# design.net
KiCad netlist of a schematic drawn in EasyEDA Pro
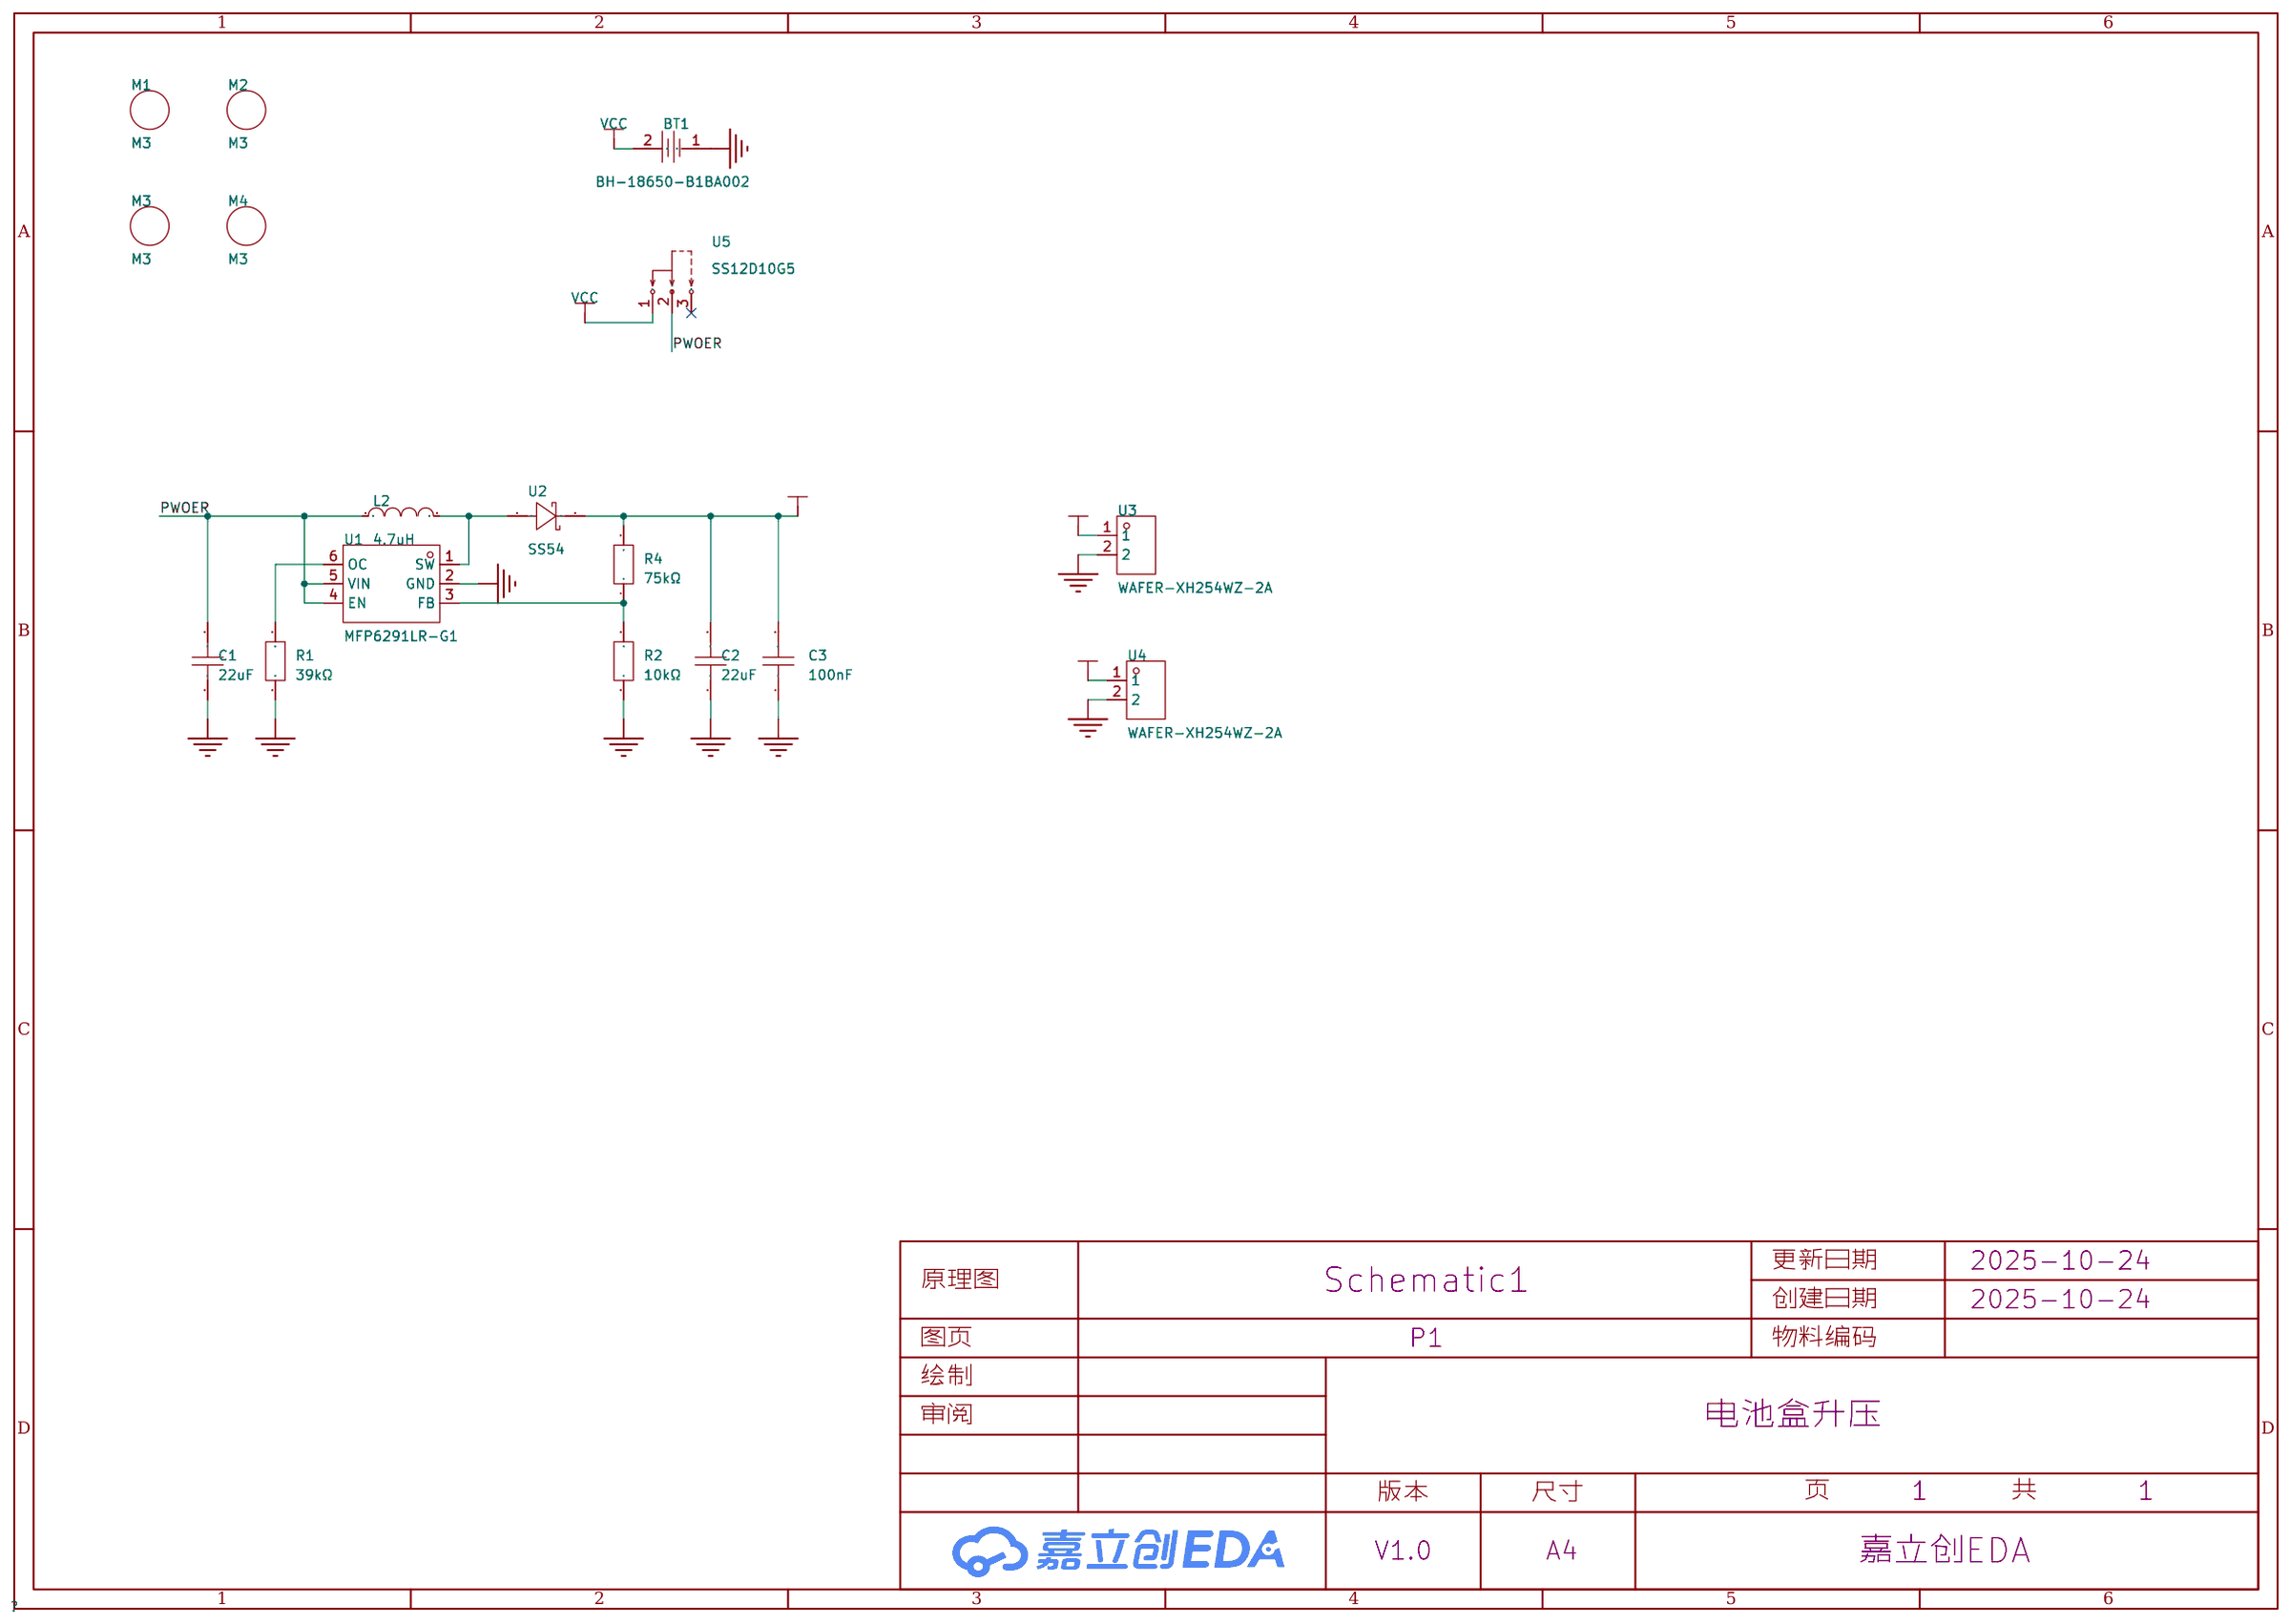
[diagram p0: schematic sheet]

(export (version "E")
  (design (tool "Eeschema 10.0.6"))
  (components
    (comp (ref "BT1")
      (value "BH-18650-B1BA002")
      (footprint "easyedapro:BATTERY-SMD_18650-1S-L77.1-W20.7-1")
      (description "连接器类型:电池盒;适用电池规格:18650;")
      (fields (field (name "Manufacturer") "MYOUNG(美阳)"))
      (libsource (lib "easyedapro") (part "BH-18650-B1BA002"))
    )
    (comp (ref "C1")
      (value "22uF")
      (footprint "easyedapro:C0805")
      (description "容值:22uF;精度:±20%;额定电压:16V;温度系数:X5R;")
      (fields
        (field (name "Manufacturer Part") "0805X5R226M160NT")
        (field (name "Manufacturer") "AIDE(爱迪电容)")
      )
      (libsource (lib "easyedapro") (part "0805X5R226M160NT"))
    )
    (comp (ref "C2")
      (value "22uF")
      (footprint "easyedapro:C0805")
      (description "容值:22uF;精度:±20%;额定电压:16V;温度系数:X5R;")
      (fields
        (field (name "Manufacturer Part") "0805X5R226M160NT")
        (field (name "Manufacturer") "AIDE(爱迪电容)")
      )
      (libsource (lib "easyedapro") (part "0805X5R226M160NT"))
    )
    (comp (ref "C3")
      (value "100nF")
      (footprint "easyedapro:C0603")
      (description "容值:100nF;精度:±20%;额定电压:50V;")
      (fields
        (field (name "Manufacturer Part") "NL0603B104M500CPBN")
        (field (name "Manufacturer") "HUI JU(汇聚)")
      )
      (libsource (lib "easyedapro") (part "NL0603B104M500CPBN"))
    )
    (comp (ref "L2")
      (value "4.7uH")
      (footprint "easyedapro:IND-SMD_L5.4-W5.2_FXL0530")
      (description "电感值:4.7uH;精度:±20%;额定电流:4.5A;饱和电流(Isat):5A;类型:一体成型电感;")
      (fields (field (name "Manufacturer Part") "FXL0530-4R7-M") (field (name "Manufacturer") "cjiang(长江微电)"))
      (libsource (lib "easyedapro") (part "FXL0530-4R7-M"))
    )
    (comp (ref "M1")
      (value "M3")
      (footprint "easyedapro:M3 125X200")
      (description "铜柱孔")
      (libsource (lib "easyedapro") (part "M3"))
    )
    (comp (ref "M2")
      (value "M3")
      (footprint "easyedapro:M3 125X200")
      (description "铜柱孔")
      (libsource (lib "easyedapro") (part "M3"))
    )
    (comp (ref "M3")
      (value "M3")
      (footprint "easyedapro:M3 125X200")
      (description "铜柱孔")
      (libsource (lib "easyedapro") (part "M3"))
    )
    (comp (ref "M4")
      (value "M3")
      (footprint "easyedapro:M3 125X200")
      (description "铜柱孔")
      (libsource (lib "easyedapro") (part "M3"))
    )
    (comp (ref "R1")
      (value "39kΩ")
      (footprint "easyedapro:R0603")
      (description "电阻类型:薄膜电阻;阻值:39kΩ;精度:±0.1%;功率:100mW;工作电压:100V;温度系数:±10ppm/°C;")
      (fields (field (name "Manufacturer Part") "PTFR0603B39K0N9") (field (name "Manufacturer") "RESI(开步睿思)"))
      (libsource (lib "easyedapro") (part "PTFR0603B39K0N9"))
    )
    (comp (ref "R2")
      (value "10kΩ")
      (footprint "easyedapro:R0603")
      (description "电阻类型:薄膜电阻;阻值:10kΩ;精度:±0.1%;功率:100mW;工作电压:75V;温度系数:±50ppm/°C;")
      (fields
        (field (name "Manufacturer Part") "TC0350B1002T5F")
        (field (name "Manufacturer") "UNI-ROYAL(厚声)")
      )
      (libsource (lib "easyedapro") (part "TC0350B1002T5F"))
    )
    (comp (ref "R4")
      (value "75kΩ")
      (footprint "easyedapro:R0603")
      (description "电阻类型:薄膜电阻;阻值:75kΩ;精度:±0.1%;功率:100mW;工作电压:100V;温度系数:±10ppm/°C;")
      (fields (field (name "Manufacturer Part") "PTFR0603B75K0N9") (field (name "Manufacturer") "RESI(开步睿思)"))
      (libsource (lib "easyedapro") (part "PTFR0603B75K0N9"))
    )
    (comp (ref "U1")
      (value "MFP6291LR-G1")
      (footprint "easyedapro:SOT-23-6_L2.9-W1.6-P0.95-LS2.8-BR")
      (description "功能类型:升压型;输出类型:可调;工作电压:2.2V~16V;输出电压:5V~20V;输出电流:2.5A;")
      (fields (field (name "Manufacturer") "MSKSEMI(美森科)"))
      (libsource (lib "easyedapro") (part "MFP6291LR-G1"))
    )
    (comp (ref "U2")
      (value "SS54")
      (footprint "easyedapro:SMB_L4.3-W3.6-LS5.4-RD")
      (description "二极管配置:独立式;正向压降(Vf):550mV@5A;直流反向耐压(Vr):40V;整流电流:5A;")
      (fields (field (name "Manufacturer") "HXY MOSFET(华轩阳电子)"))
      (libsource (lib "easyedapro") (part "SS54_C5200096"))
    )
    (comp (ref "U3")
      (value "WAFER-XH254WZ-2A")
      (footprint "easyedapro:CONN-TH_2P-P2.50_WAFER-XH254WZ-2A")
      (description "插针结构:1x2P;间距:2.54mm;安装方式:弯插;参考系列:XH;总PIN数:2P;排数:1;每排PIN数:2;额定电流:3A;触头材质:黄铜;工作温度:-25°C~+85°C;")
      (fields (field (name "Manufacturer") "HANBO(汉博)"))
      (libsource (lib "easyedapro") (part "WAFER-XH254WZ-2A"))
    )
    (comp (ref "U4")
      (value "WAFER-XH254WZ-2A")
      (footprint "easyedapro:CONN-TH_2P-P2.50_WAFER-XH254WZ-2A")
      (description "插针结构:1x2P;间距:2.54mm;安装方式:弯插;参考系列:XH;总PIN数:2P;排数:1;每排PIN数:2;额定电流:3A;触头材质:黄铜;工作温度:-25°C~+85°C;")
      (fields (field (name "Manufacturer") "HANBO(汉博)"))
      (libsource (lib "easyedapro") (part "WAFER-XH254WZ-2A"))
    )
    (comp (ref "U5")
      (value "SS12D10G5")
      (footprint "easyedapro:SW-TH_SHOU-HAN_SS12D10G4")
      (description "电路结构:单刀双掷;安装方式:直插;额定电流:2A;额定电压:125V;工作寿命:3千次;")
      (fields (field (name "Manufacturer") "SHOU HAN(首韩)"))
      (libsource (lib "easyedapro") (part "SS12D10G5"))
    )
  )
  (nets
    (net (code "1") (name "/PWOER") (class "Default")
      (node (ref "C1") (pin "2") (pinfunction "2_2") (pintype "unspecified"))
      (node (ref "L2") (pin "1") (pinfunction "1_1") (pintype "unspecified"))
      (node (ref "U1") (pin "4") (pinfunction "EN_4") (pintype "unspecified"))
      (node (ref "U1") (pin "5") (pinfunction "VIN_5") (pintype "unspecified"))
      (node (ref "U5") (pin "2") (pinfunction "2_2") (pintype "unspecified"))
    )
    (net (code "2") (name "GND") (class "Default")
      (node (ref "BT1") (pin "1") (pinfunction "1_1") (pintype "input"))
      (node (ref "C1") (pin "1") (pinfunction "1_1") (pintype "unspecified"))
      (node (ref "C2") (pin "1") (pinfunction "1_1") (pintype "unspecified"))
      (node (ref "C3") (pin "1") (pinfunction "1_1") (pintype "unspecified"))
      (node (ref "R1") (pin "1") (pinfunction "1_1") (pintype "unspecified"))
      (node (ref "R2") (pin "1") (pinfunction "1_1") (pintype "unspecified"))
      (node (ref "U1") (pin "2") (pinfunction "GND_2") (pintype "unspecified"))
      (node (ref "U3") (pin "2") (pinfunction "2_2") (pintype "unspecified"))
      (node (ref "U4") (pin "2") (pinfunction "2_2") (pintype "unspecified"))
    )
    (net (code "3") (name "Net-(U1-FB)") (class "Default")
      (node (ref "R2") (pin "2") (pinfunction "2_2") (pintype "unspecified"))
      (node (ref "R4") (pin "1") (pinfunction "1_1") (pintype "unspecified"))
      (node (ref "U1") (pin "3") (pinfunction "FB_3") (pintype "unspecified"))
    )
    (net (code "4") (name "Net-(U1-OC)") (class "Default")
      (node (ref "R1") (pin "2") (pinfunction "2_2") (pintype "unspecified"))
      (node (ref "U1") (pin "6") (pinfunction "OC_6") (pintype "unspecified"))
    )
    (net (code "5") (name "Net-(U1-SW)") (class "Default")
      (node (ref "L2") (pin "2") (pinfunction "2_2") (pintype "unspecified"))
      (node (ref "U1") (pin "1") (pinfunction "SW_1") (pintype "unspecified"))
      (node (ref "U2") (pin "2") (pinfunction "2_2") (pintype "unspecified"))
    )
    (net (code "6") (name "VCC") (class "Default")
      (node (ref "BT1") (pin "2") (pinfunction "2_2") (pintype "input"))
      (node (ref "U5") (pin "1") (pinfunction "1_1") (pintype "unspecified"))
    )
    (net (code "7") (name "VOUT") (class "Default")
      (node (ref "C2") (pin "2") (pinfunction "2_2") (pintype "unspecified"))
      (node (ref "C3") (pin "2") (pinfunction "2_2") (pintype "unspecified"))
      (node (ref "R4") (pin "2") (pinfunction "2_2") (pintype "unspecified"))
      (node (ref "U2") (pin "1") (pinfunction "1_1") (pintype "unspecified"))
      (node (ref "U3") (pin "1") (pinfunction "1_1") (pintype "unspecified"))
      (node (ref "U4") (pin "1") (pinfunction "1_1") (pintype "unspecified"))
    )
    (net (code "8") (name "unconnected-(U5-Pad3)") (class "Default")
      (node (ref "U5") (pin "3") (pinfunction "3_3") (pintype "unspecified+no_connect"))
    )
  )
)
